# relay_5channel.net
KiCad netlist of a schematic drawn in EAGLE
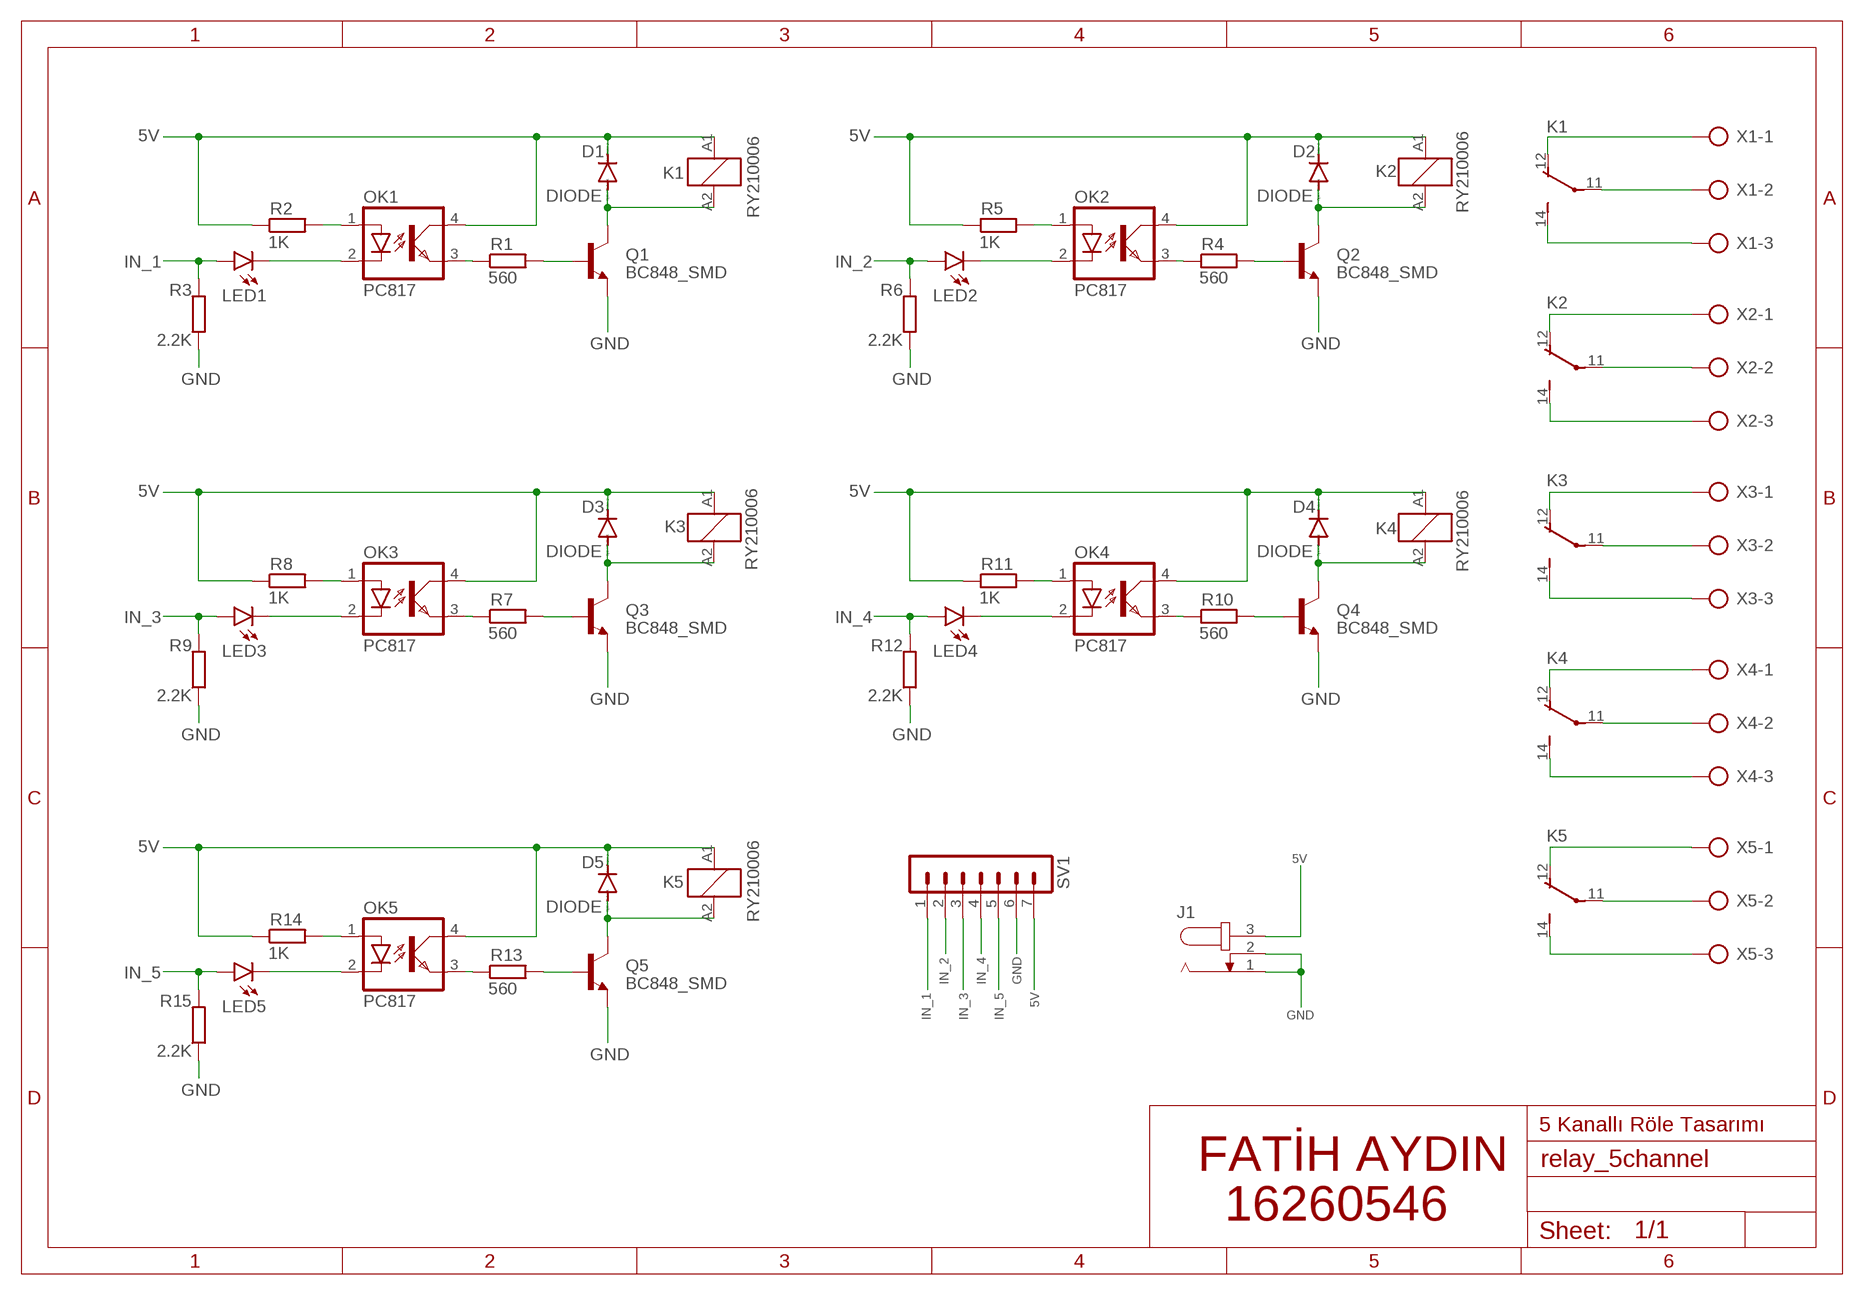
[diagram p0: schematic, sheet 1]

(export (version "E")
  (design (tool "Eeschema 10.0.6"))
  (components
    (comp (ref "D1")
      (value "DIODE")
      (footprint "eagle-import:DO35-7")
      (libsource (lib "eagle-import") (part "1N4148DO35-7"))
    )
    (comp (ref "D2")
      (value "DIODE")
      (footprint "eagle-import:DO35-7")
      (libsource (lib "eagle-import") (part "1N4148DO35-7"))
    )
    (comp (ref "D3")
      (value "DIODE")
      (footprint "eagle-import:DO35-7")
      (libsource (lib "eagle-import") (part "1N4148DO35-7"))
    )
    (comp (ref "D4")
      (value "DIODE")
      (footprint "eagle-import:DO35-7")
      (libsource (lib "eagle-import") (part "1N4148DO35-7"))
    )
    (comp (ref "D5")
      (value "DIODE")
      (footprint "eagle-import:DO35-7")
      (libsource (lib "eagle-import") (part "1N4148DO35-7"))
    )
    (comp (ref "J1")
      (value "JACK-PLUG1")
      (footprint "eagle-import:SPC4078")
      (libsource (lib "eagle-import") (part "JACK-PLUG1"))
    )
    (comp (ref "K1")
      (value "RY210006")
      (footprint "eagle-import:RY-II")
      (fields (field (name "MF") "TYCO ELECTRONICS"))
      (libsource (lib "eagle-import") (part "RY?120006"))
    )
    (comp (ref "K2")
      (value "RY210006")
      (footprint "eagle-import:RY-II")
      (fields (field (name "MF") "TYCO ELECTRONICS"))
      (libsource (lib "eagle-import") (part "RY?120006"))
    )
    (comp (ref "K3")
      (value "RY210006")
      (footprint "eagle-import:RY-II")
      (fields (field (name "MF") "TYCO ELECTRONICS"))
      (libsource (lib "eagle-import") (part "RY?120006"))
    )
    (comp (ref "K4")
      (value "RY210006")
      (footprint "eagle-import:RY-II")
      (fields (field (name "MF") "TYCO ELECTRONICS"))
      (libsource (lib "eagle-import") (part "RY?120006"))
    )
    (comp (ref "K5")
      (value "RY210006")
      (footprint "eagle-import:RY-II")
      (fields (field (name "MF") "TYCO ELECTRONICS"))
      (libsource (lib "eagle-import") (part "RY?120006"))
    )
    (comp (ref "LED1")
      (value "LEDCHIP-LED0805")
      (footprint "eagle-import:CHIP-LED0805")
      (libsource (lib "eagle-import") (part "LEDCHIP-LED0805"))
    )
    (comp (ref "LED2")
      (value "LEDCHIP-LED0805")
      (footprint "eagle-import:CHIP-LED0805")
      (libsource (lib "eagle-import") (part "LEDCHIP-LED0805"))
    )
    (comp (ref "LED3")
      (value "LEDCHIP-LED0805")
      (footprint "eagle-import:CHIP-LED0805")
      (libsource (lib "eagle-import") (part "LEDCHIP-LED0805"))
    )
    (comp (ref "LED4")
      (value "LEDCHIP-LED0805")
      (footprint "eagle-import:CHIP-LED0805")
      (libsource (lib "eagle-import") (part "LEDCHIP-LED0805"))
    )
    (comp (ref "LED5")
      (value "LEDCHIP-LED0805")
      (footprint "eagle-import:CHIP-LED0805")
      (libsource (lib "eagle-import") (part "LEDCHIP-LED0805"))
    )
    (comp (ref "OK1")
      (value "PC817")
      (footprint "eagle-import:DIL04")
      (fields (field (name "MPN") "PC817X4J000F"))
      (libsource (lib "eagle-import") (part "PC817"))
    )
    (comp (ref "OK2")
      (value "PC817")
      (footprint "eagle-import:DIL04")
      (fields (field (name "MPN") "PC817X4J000F"))
      (libsource (lib "eagle-import") (part "PC817"))
    )
    (comp (ref "OK3")
      (value "PC817")
      (footprint "eagle-import:DIL04")
      (fields (field (name "MPN") "PC817X4J000F"))
      (libsource (lib "eagle-import") (part "PC817"))
    )
    (comp (ref "OK4")
      (value "PC817")
      (footprint "eagle-import:DIL04")
      (fields (field (name "MPN") "PC817X4J000F"))
      (libsource (lib "eagle-import") (part "PC817"))
    )
    (comp (ref "OK5")
      (value "PC817")
      (footprint "eagle-import:DIL04")
      (fields (field (name "MPN") "PC817X4J000F"))
      (libsource (lib "eagle-import") (part "PC817"))
    )
    (comp (ref "Q1")
      (value "BC848_SMD")
      (footprint "eagle-import:SOT23")
      (libsource (lib "eagle-import") (part "BC848SMDALT1"))
    )
    (comp (ref "Q2")
      (value "BC848_SMD")
      (footprint "eagle-import:SOT23")
      (libsource (lib "eagle-import") (part "BC848SMDALT1"))
    )
    (comp (ref "Q3")
      (value "BC848_SMD")
      (footprint "eagle-import:SOT23")
      (libsource (lib "eagle-import") (part "BC848SMDALT1"))
    )
    (comp (ref "Q4")
      (value "BC848_SMD")
      (footprint "eagle-import:SOT23")
      (libsource (lib "eagle-import") (part "BC848SMDALT1"))
    )
    (comp (ref "Q5")
      (value "BC848_SMD")
      (footprint "eagle-import:SOT23")
      (libsource (lib "eagle-import") (part "BC848SMDALT1"))
    )
    (comp (ref "R1")
      (value "560")
      (footprint "eagle-import:M0805")
      (libsource (lib "eagle-import") (part "R-EU_M0805"))
    )
    (comp (ref "R2")
      (value "1K")
      (footprint "eagle-import:0204_5")
      (libsource (lib "eagle-import") (part "R-EU_0204/5"))
    )
    (comp (ref "R3")
      (value "2.2K")
      (footprint "eagle-import:0204_5")
      (libsource (lib "eagle-import") (part "R-EU_0204/5"))
    )
    (comp (ref "R4")
      (value "560")
      (footprint "eagle-import:M0805")
      (libsource (lib "eagle-import") (part "R-EU_M0805"))
    )
    (comp (ref "R5")
      (value "1K")
      (footprint "eagle-import:0204_5")
      (libsource (lib "eagle-import") (part "R-EU_0204/5"))
    )
    (comp (ref "R6")
      (value "2.2K")
      (footprint "eagle-import:0204_5")
      (libsource (lib "eagle-import") (part "R-EU_0204/5"))
    )
    (comp (ref "R7")
      (value "560")
      (footprint "eagle-import:M0805")
      (libsource (lib "eagle-import") (part "R-EU_M0805"))
    )
    (comp (ref "R8")
      (value "1K")
      (footprint "eagle-import:0204_5")
      (libsource (lib "eagle-import") (part "R-EU_0204/5"))
    )
    (comp (ref "R9")
      (value "2.2K")
      (footprint "eagle-import:0204_5")
      (libsource (lib "eagle-import") (part "R-EU_0204/5"))
    )
    (comp (ref "R10")
      (value "560")
      (footprint "eagle-import:M0805")
      (libsource (lib "eagle-import") (part "R-EU_M0805"))
    )
    (comp (ref "R11")
      (value "1K")
      (footprint "eagle-import:0204_5")
      (libsource (lib "eagle-import") (part "R-EU_0204/5"))
    )
    (comp (ref "R12")
      (value "2.2K")
      (footprint "eagle-import:0204_5")
      (libsource (lib "eagle-import") (part "R-EU_0204/5"))
    )
    (comp (ref "R13")
      (value "560")
      (footprint "eagle-import:M0805")
      (libsource (lib "eagle-import") (part "R-EU_M0805"))
    )
    (comp (ref "R14")
      (value "1K")
      (footprint "eagle-import:0204_5")
      (libsource (lib "eagle-import") (part "R-EU_0204/5"))
    )
    (comp (ref "R15")
      (value "2.2K")
      (footprint "eagle-import:0204_5")
      (libsource (lib "eagle-import") (part "R-EU_0204/5"))
    )
    (comp (ref "SV1")
      (value "MA07-1")
      (footprint "eagle-import:MA07-1")
      (libsource (lib "eagle-import") (part "MA07-1"))
    )
    (comp (ref "X1")
      (value "AK300/3")
      (footprint "eagle-import:AK300_3")
      (libsource (lib "eagle-import") (part "AK300/3"))
    )
    (comp (ref "X2")
      (value "AK300/3")
      (footprint "eagle-import:AK300_3")
      (libsource (lib "eagle-import") (part "AK300/3"))
    )
    (comp (ref "X3")
      (value "AK300/3")
      (footprint "eagle-import:AK300_3")
      (libsource (lib "eagle-import") (part "AK300/3"))
    )
    (comp (ref "X4")
      (value "AK300/3")
      (footprint "eagle-import:AK300_3")
      (libsource (lib "eagle-import") (part "AK300/3"))
    )
    (comp (ref "X5")
      (value "AK300/3")
      (footprint "eagle-import:AK300_3")
      (libsource (lib "eagle-import") (part "AK300/3"))
    )
  )
  (nets
    (net (code "1") (name "/5V") (class "Default")
      (node (ref "D1") (pin "C") (pinfunction "C_C") (pintype "passive"))
      (node (ref "D2") (pin "C") (pinfunction "C_C") (pintype "passive"))
      (node (ref "D3") (pin "C") (pinfunction "C_C") (pintype "passive"))
      (node (ref "D4") (pin "C") (pinfunction "C_C") (pintype "passive"))
      (node (ref "D5") (pin "C") (pinfunction "C_C") (pintype "passive"))
      (node (ref "J1") (pin "3") (pinfunction "3_3") (pintype "passive"))
      (node (ref "K1") (pin "A1") (pinfunction "1_A1") (pintype "passive"))
      (node (ref "K2") (pin "A1") (pinfunction "1_A1") (pintype "passive"))
      (node (ref "K3") (pin "A1") (pinfunction "1_A1") (pintype "passive"))
      (node (ref "K4") (pin "A1") (pinfunction "1_A1") (pintype "passive"))
      (node (ref "K5") (pin "A1") (pinfunction "1_A1") (pintype "passive"))
      (node (ref "OK1") (pin "4") (pinfunction "COL_4") (pintype "passive"))
      (node (ref "OK2") (pin "4") (pinfunction "COL_4") (pintype "passive"))
      (node (ref "OK3") (pin "4") (pinfunction "COL_4") (pintype "passive"))
      (node (ref "OK4") (pin "4") (pinfunction "COL_4") (pintype "passive"))
      (node (ref "OK5") (pin "4") (pinfunction "COL_4") (pintype "passive"))
      (node (ref "R11") (pin "1") (pinfunction "1_1") (pintype "passive"))
      (node (ref "R14") (pin "1") (pinfunction "1_1") (pintype "passive"))
      (node (ref "R2") (pin "1") (pinfunction "1_1") (pintype "passive"))
      (node (ref "R5") (pin "1") (pinfunction "1_1") (pintype "passive"))
      (node (ref "R8") (pin "1") (pinfunction "1_1") (pintype "passive"))
      (node (ref "SV1") (pin "7") (pinfunction "7_7") (pintype "passive"))
    )
    (net (code "2") (name "/GND") (class "Default")
      (node (ref "J1") (pin "1") (pinfunction "1_1") (pintype "passive"))
      (node (ref "J1") (pin "2") (pinfunction "2_2") (pintype "passive"))
      (node (ref "Q1") (pin "2") (pinfunction "E_2") (pintype "passive"))
      (node (ref "Q2") (pin "2") (pinfunction "E_2") (pintype "passive"))
      (node (ref "Q3") (pin "2") (pinfunction "E_2") (pintype "passive"))
      (node (ref "Q4") (pin "2") (pinfunction "E_2") (pintype "passive"))
      (node (ref "Q5") (pin "2") (pinfunction "E_2") (pintype "passive"))
      (node (ref "R12") (pin "1") (pinfunction "1_1") (pintype "passive"))
      (node (ref "R15") (pin "1") (pinfunction "1_1") (pintype "passive"))
      (node (ref "R3") (pin "1") (pinfunction "1_1") (pintype "passive"))
      (node (ref "R6") (pin "1") (pinfunction "1_1") (pintype "passive"))
      (node (ref "R9") (pin "1") (pinfunction "1_1") (pintype "passive"))
      (node (ref "SV1") (pin "6") (pinfunction "6_6") (pintype "passive"))
    )
    (net (code "3") (name "/IN_1") (class "Default")
      (node (ref "LED1") (pin "A") (pinfunction "A_A") (pintype "passive"))
      (node (ref "R3") (pin "2") (pinfunction "2_2") (pintype "passive"))
      (node (ref "SV1") (pin "1") (pinfunction "1_1") (pintype "passive"))
    )
    (net (code "4") (name "/IN_2") (class "Default")
      (node (ref "LED2") (pin "A") (pinfunction "A_A") (pintype "passive"))
      (node (ref "R6") (pin "2") (pinfunction "2_2") (pintype "passive"))
      (node (ref "SV1") (pin "2") (pinfunction "2_2") (pintype "passive"))
    )
    (net (code "5") (name "/IN_3") (class "Default")
      (node (ref "LED3") (pin "A") (pinfunction "A_A") (pintype "passive"))
      (node (ref "R9") (pin "2") (pinfunction "2_2") (pintype "passive"))
      (node (ref "SV1") (pin "3") (pinfunction "3_3") (pintype "passive"))
    )
    (net (code "6") (name "/IN_4") (class "Default")
      (node (ref "LED4") (pin "A") (pinfunction "A_A") (pintype "passive"))
      (node (ref "R12") (pin "2") (pinfunction "2_2") (pintype "passive"))
      (node (ref "SV1") (pin "4") (pinfunction "4_4") (pintype "passive"))
    )
    (net (code "7") (name "/IN_5") (class "Default")
      (node (ref "LED5") (pin "A") (pinfunction "A_A") (pintype "passive"))
      (node (ref "R15") (pin "2") (pinfunction "2_2") (pintype "passive"))
      (node (ref "SV1") (pin "5") (pinfunction "5_5") (pintype "passive"))
    )
    (net (code "8") (name "Net-(K1A-2)") (class "Default")
      (node (ref "D1") (pin "A") (pinfunction "A_A") (pintype "passive"))
      (node (ref "K1") (pin "A2") (pinfunction "2_A2") (pintype "passive"))
      (node (ref "Q1") (pin "3") (pinfunction "C_3") (pintype "passive"))
    )
    (net (code "9") (name "Net-(K1B-O)") (class "Default")
      (node (ref "K1") (pin "12") (pinfunction "O_12") (pintype "passive"))
      (node (ref "X1") (pin "1") (pinfunction "KL_1") (pintype "passive"))
    )
    (net (code "10") (name "Net-(K1B-P)") (class "Default")
      (node (ref "K1") (pin "11") (pinfunction "P_11") (pintype "passive"))
      (node (ref "X1") (pin "2") (pinfunction "KL_2") (pintype "passive"))
    )
    (net (code "11") (name "Net-(K1B-S)") (class "Default")
      (node (ref "K1") (pin "14") (pinfunction "S_14") (pintype "passive"))
      (node (ref "X1") (pin "3") (pinfunction "KL_3") (pintype "passive"))
    )
    (net (code "12") (name "Net-(K2A-2)") (class "Default")
      (node (ref "D2") (pin "A") (pinfunction "A_A") (pintype "passive"))
      (node (ref "K2") (pin "A2") (pinfunction "2_A2") (pintype "passive"))
      (node (ref "Q2") (pin "3") (pinfunction "C_3") (pintype "passive"))
    )
    (net (code "13") (name "Net-(K2B-O)") (class "Default")
      (node (ref "K2") (pin "12") (pinfunction "O_12") (pintype "passive"))
      (node (ref "X2") (pin "1") (pinfunction "KL_1") (pintype "passive"))
    )
    (net (code "14") (name "Net-(K2B-P)") (class "Default")
      (node (ref "K2") (pin "11") (pinfunction "P_11") (pintype "passive"))
      (node (ref "X2") (pin "2") (pinfunction "KL_2") (pintype "passive"))
    )
    (net (code "15") (name "Net-(K2B-S)") (class "Default")
      (node (ref "K2") (pin "14") (pinfunction "S_14") (pintype "passive"))
      (node (ref "X2") (pin "3") (pinfunction "KL_3") (pintype "passive"))
    )
    (net (code "16") (name "Net-(K3A-2)") (class "Default")
      (node (ref "D3") (pin "A") (pinfunction "A_A") (pintype "passive"))
      (node (ref "K3") (pin "A2") (pinfunction "2_A2") (pintype "passive"))
      (node (ref "Q3") (pin "3") (pinfunction "C_3") (pintype "passive"))
    )
    (net (code "17") (name "Net-(K3B-O)") (class "Default")
      (node (ref "K3") (pin "12") (pinfunction "O_12") (pintype "passive"))
      (node (ref "X3") (pin "1") (pinfunction "KL_1") (pintype "passive"))
    )
    (net (code "18") (name "Net-(K3B-P)") (class "Default")
      (node (ref "K3") (pin "11") (pinfunction "P_11") (pintype "passive"))
      (node (ref "X3") (pin "2") (pinfunction "KL_2") (pintype "passive"))
    )
    (net (code "19") (name "Net-(K3B-S)") (class "Default")
      (node (ref "K3") (pin "14") (pinfunction "S_14") (pintype "passive"))
      (node (ref "X3") (pin "3") (pinfunction "KL_3") (pintype "passive"))
    )
    (net (code "20") (name "Net-(K4A-2)") (class "Default")
      (node (ref "D4") (pin "A") (pinfunction "A_A") (pintype "passive"))
      (node (ref "K4") (pin "A2") (pinfunction "2_A2") (pintype "passive"))
      (node (ref "Q4") (pin "3") (pinfunction "C_3") (pintype "passive"))
    )
    (net (code "21") (name "Net-(K4B-O)") (class "Default")
      (node (ref "K4") (pin "12") (pinfunction "O_12") (pintype "passive"))
      (node (ref "X4") (pin "1") (pinfunction "KL_1") (pintype "passive"))
    )
    (net (code "22") (name "Net-(K4B-P)") (class "Default")
      (node (ref "K4") (pin "11") (pinfunction "P_11") (pintype "passive"))
      (node (ref "X4") (pin "2") (pinfunction "KL_2") (pintype "passive"))
    )
    (net (code "23") (name "Net-(K4B-S)") (class "Default")
      (node (ref "K4") (pin "14") (pinfunction "S_14") (pintype "passive"))
      (node (ref "X4") (pin "3") (pinfunction "KL_3") (pintype "passive"))
    )
    (net (code "24") (name "Net-(K5A-2)") (class "Default")
      (node (ref "D5") (pin "A") (pinfunction "A_A") (pintype "passive"))
      (node (ref "K5") (pin "A2") (pinfunction "2_A2") (pintype "passive"))
      (node (ref "Q5") (pin "3") (pinfunction "C_3") (pintype "passive"))
    )
    (net (code "25") (name "Net-(K5B-O)") (class "Default")
      (node (ref "K5") (pin "12") (pinfunction "O_12") (pintype "passive"))
      (node (ref "X5") (pin "1") (pinfunction "KL_1") (pintype "passive"))
    )
    (net (code "26") (name "Net-(K5B-P)") (class "Default")
      (node (ref "K5") (pin "11") (pinfunction "P_11") (pintype "passive"))
      (node (ref "X5") (pin "2") (pinfunction "KL_2") (pintype "passive"))
    )
    (net (code "27") (name "Net-(K5B-S)") (class "Default")
      (node (ref "K5") (pin "14") (pinfunction "S_14") (pintype "passive"))
      (node (ref "X5") (pin "3") (pinfunction "KL_3") (pintype "passive"))
    )
    (net (code "28") (name "Net-(OK1-A)") (class "Default")
      (node (ref "OK1") (pin "1") (pinfunction "A_1") (pintype "passive"))
      (node (ref "R2") (pin "2") (pinfunction "2_2") (pintype "passive"))
    )
    (net (code "29") (name "Net-(OK1-C)") (class "Default")
      (node (ref "LED1") (pin "C") (pinfunction "C_C") (pintype "passive"))
      (node (ref "OK1") (pin "2") (pinfunction "C_2") (pintype "passive"))
    )
    (net (code "30") (name "Net-(OK1-EMIT)") (class "Default")
      (node (ref "OK1") (pin "3") (pinfunction "EMIT_3") (pintype "passive"))
      (node (ref "R1") (pin "1") (pinfunction "1_1") (pintype "passive"))
    )
    (net (code "31") (name "Net-(OK2-A)") (class "Default")
      (node (ref "OK2") (pin "1") (pinfunction "A_1") (pintype "passive"))
      (node (ref "R5") (pin "2") (pinfunction "2_2") (pintype "passive"))
    )
    (net (code "32") (name "Net-(OK2-C)") (class "Default")
      (node (ref "LED2") (pin "C") (pinfunction "C_C") (pintype "passive"))
      (node (ref "OK2") (pin "2") (pinfunction "C_2") (pintype "passive"))
    )
    (net (code "33") (name "Net-(OK2-EMIT)") (class "Default")
      (node (ref "OK2") (pin "3") (pinfunction "EMIT_3") (pintype "passive"))
      (node (ref "R4") (pin "1") (pinfunction "1_1") (pintype "passive"))
    )
    (net (code "34") (name "Net-(OK3-A)") (class "Default")
      (node (ref "OK3") (pin "1") (pinfunction "A_1") (pintype "passive"))
      (node (ref "R8") (pin "2") (pinfunction "2_2") (pintype "passive"))
    )
    (net (code "35") (name "Net-(OK3-C)") (class "Default")
      (node (ref "LED3") (pin "C") (pinfunction "C_C") (pintype "passive"))
      (node (ref "OK3") (pin "2") (pinfunction "C_2") (pintype "passive"))
    )
    (net (code "36") (name "Net-(OK3-EMIT)") (class "Default")
      (node (ref "OK3") (pin "3") (pinfunction "EMIT_3") (pintype "passive"))
      (node (ref "R7") (pin "1") (pinfunction "1_1") (pintype "passive"))
    )
    (net (code "37") (name "Net-(OK4-A)") (class "Default")
      (node (ref "OK4") (pin "1") (pinfunction "A_1") (pintype "passive"))
      (node (ref "R11") (pin "2") (pinfunction "2_2") (pintype "passive"))
    )
    (net (code "38") (name "Net-(OK4-C)") (class "Default")
      (node (ref "LED4") (pin "C") (pinfunction "C_C") (pintype "passive"))
      (node (ref "OK4") (pin "2") (pinfunction "C_2") (pintype "passive"))
    )
    (net (code "39") (name "Net-(OK4-EMIT)") (class "Default")
      (node (ref "OK4") (pin "3") (pinfunction "EMIT_3") (pintype "passive"))
      (node (ref "R10") (pin "1") (pinfunction "1_1") (pintype "passive"))
    )
    (net (code "40") (name "Net-(OK5-A)") (class "Default")
      (node (ref "OK5") (pin "1") (pinfunction "A_1") (pintype "passive"))
      (node (ref "R14") (pin "2") (pinfunction "2_2") (pintype "passive"))
    )
    (net (code "41") (name "Net-(OK5-C)") (class "Default")
      (node (ref "LED5") (pin "C") (pinfunction "C_C") (pintype "passive"))
      (node (ref "OK5") (pin "2") (pinfunction "C_2") (pintype "passive"))
    )
    (net (code "42") (name "Net-(OK5-EMIT)") (class "Default")
      (node (ref "OK5") (pin "3") (pinfunction "EMIT_3") (pintype "passive"))
      (node (ref "R13") (pin "1") (pinfunction "1_1") (pintype "passive"))
    )
    (net (code "43") (name "Net-(Q1-B)") (class "Default")
      (node (ref "Q1") (pin "1") (pinfunction "B_1") (pintype "passive"))
      (node (ref "R1") (pin "2") (pinfunction "2_2") (pintype "passive"))
    )
    (net (code "44") (name "Net-(Q2-B)") (class "Default")
      (node (ref "Q2") (pin "1") (pinfunction "B_1") (pintype "passive"))
      (node (ref "R4") (pin "2") (pinfunction "2_2") (pintype "passive"))
    )
    (net (code "45") (name "Net-(Q3-B)") (class "Default")
      (node (ref "Q3") (pin "1") (pinfunction "B_1") (pintype "passive"))
      (node (ref "R7") (pin "2") (pinfunction "2_2") (pintype "passive"))
    )
    (net (code "46") (name "Net-(Q4-B)") (class "Default")
      (node (ref "Q4") (pin "1") (pinfunction "B_1") (pintype "passive"))
      (node (ref "R10") (pin "2") (pinfunction "2_2") (pintype "passive"))
    )
    (net (code "47") (name "Net-(Q5-B)") (class "Default")
      (node (ref "Q5") (pin "1") (pinfunction "B_1") (pintype "passive"))
      (node (ref "R13") (pin "2") (pinfunction "2_2") (pintype "passive"))
    )
  )
)
